# Grove_-_Differential_Amplifier_v1_2.net
KiCad netlist of a schematic drawn in EAGLE
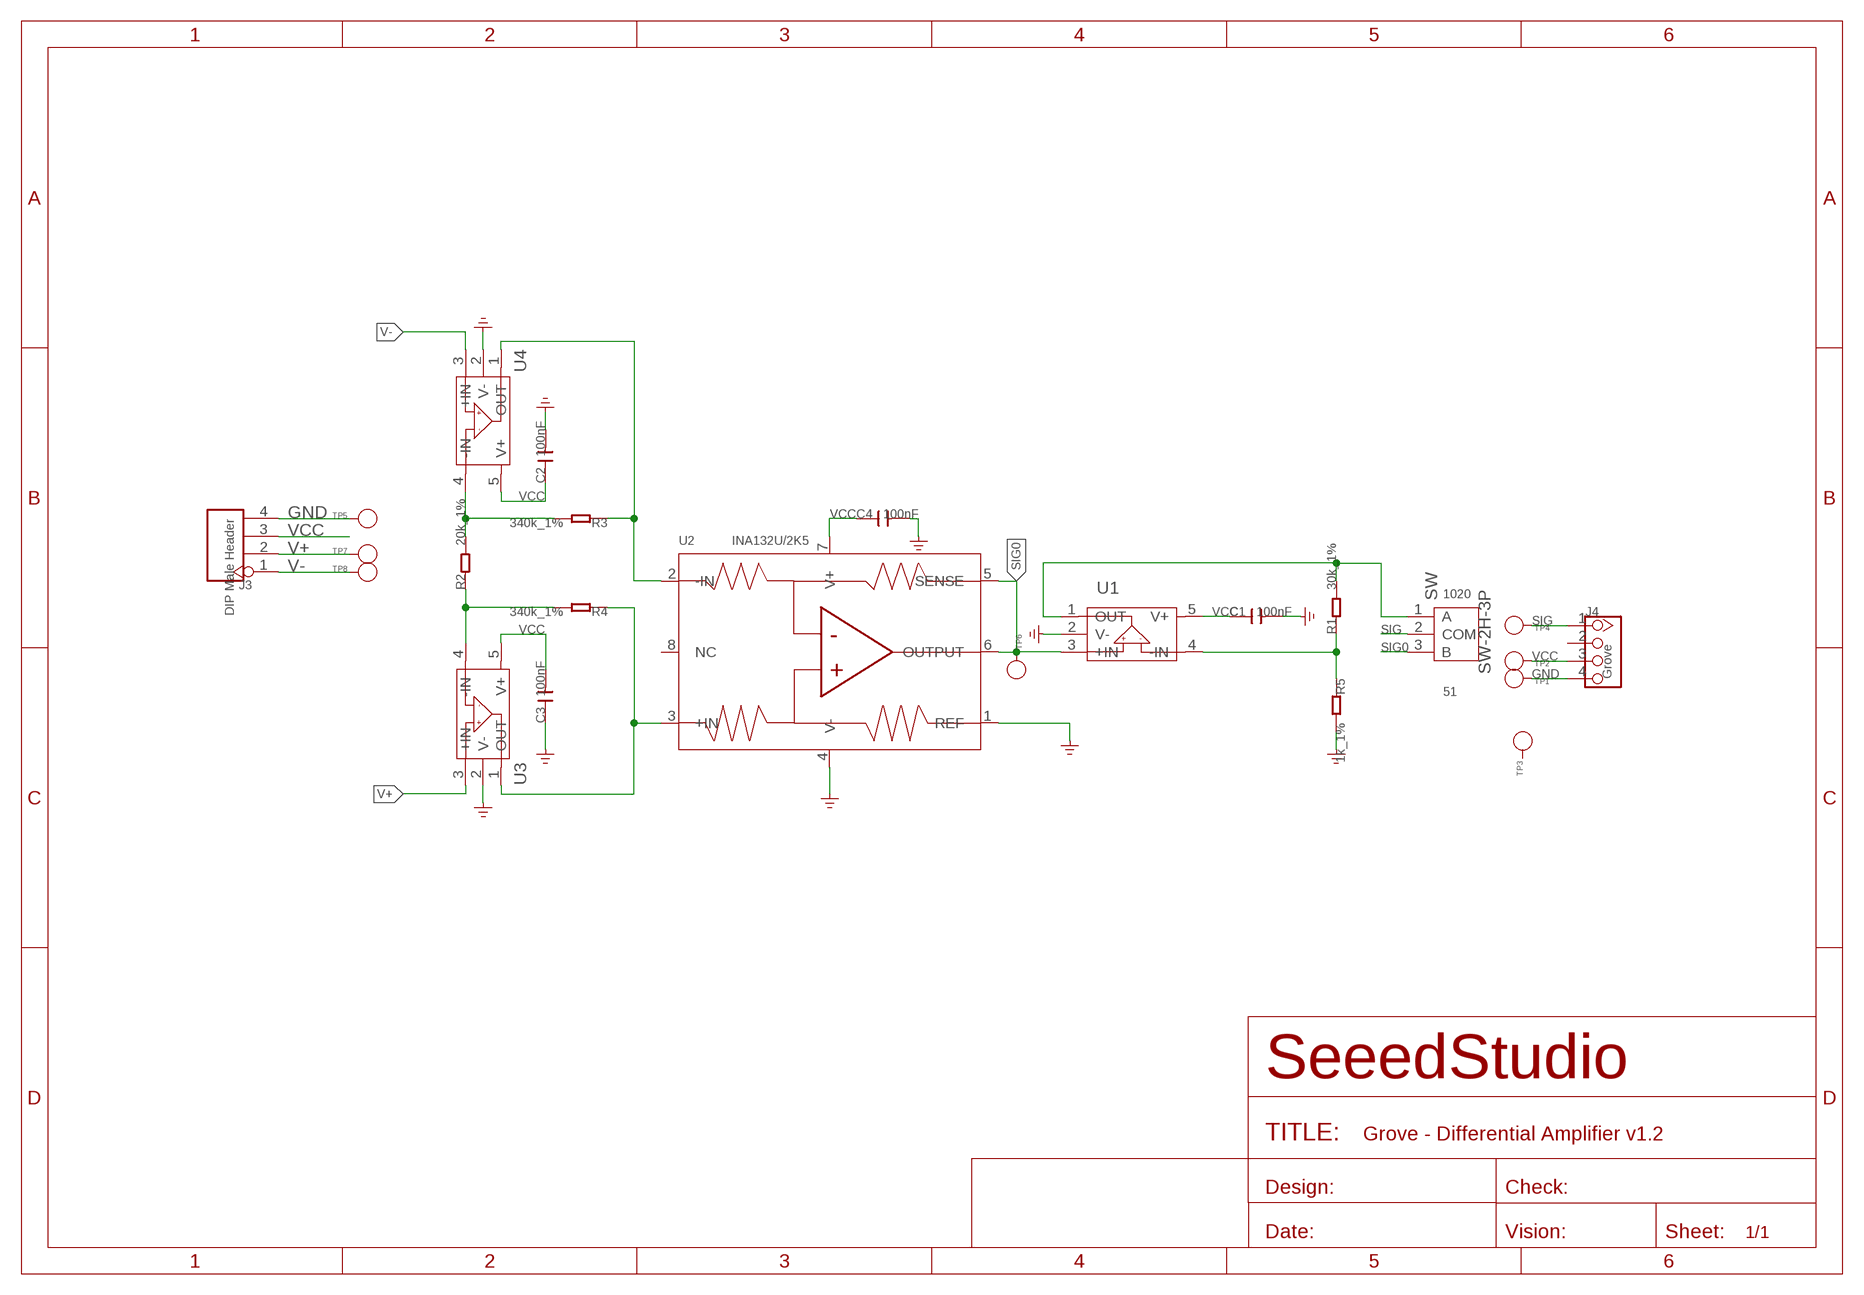
[diagram p0: schematic, sheet 1]

(export (version "E")
  (design (tool "Eeschema 10.0.6"))
  (components
    (comp (ref "C1")
      (value "100nF")
      (footprint "eagle-import:C0603")
      (libsource (lib "eagle-import") (part "C-0603"))
    )
    (comp (ref "C2")
      (value "100nF")
      (footprint "eagle-import:C0603")
      (libsource (lib "eagle-import") (part "C-0603"))
    )
    (comp (ref "C3")
      (value "100nF")
      (footprint "eagle-import:C0603")
      (libsource (lib "eagle-import") (part "C-0603"))
    )
    (comp (ref "C4")
      (value "100nF")
      (footprint "eagle-import:C0603")
      (libsource (lib "eagle-import") (part "C-0603"))
    )
    (comp (ref "J3")
      (value "DIP Male Header")
      (footprint "eagle-import:4P-65_35MIL")
      (libsource (lib "eagle-import") (part "HEADER-4P-65/35MIL"))
    )
    (comp (ref "J4")
      (value "Grove")
      (footprint "eagle-import:4P-2.0")
      (libsource (lib "eagle-import") (part "TWIG-4P-2.0-2.0"))
    )
    (comp (ref "R1")
      (value "30k_1%")
      (footprint "eagle-import:R0603")
      (libsource (lib "eagle-import") (part "R-0603"))
    )
    (comp (ref "R2")
      (value "20k_1%")
      (footprint "eagle-import:R0603")
      (libsource (lib "eagle-import") (part "R-0603"))
    )
    (comp (ref "R3")
      (value "340k_1%")
      (footprint "eagle-import:R0603")
      (libsource (lib "eagle-import") (part "R-0603"))
    )
    (comp (ref "R4")
      (value "340k_1%")
      (footprint "eagle-import:R0603")
      (libsource (lib "eagle-import") (part "R-0603"))
    )
    (comp (ref "R5")
      (value "1k_1%")
      (footprint "eagle-import:R0603")
      (libsource (lib "eagle-import") (part "R-0603"))
    )
    (comp (ref "SW")
      (value "SW-2H-3P")
      (footprint "eagle-import:3P-2CH-3.54X8.5")
      (libsource (lib "eagle-import") (part "SWITCH-2H-3P'--'"))
    )
    (comp (ref "TP1")
      (value "PAD-TEST-POINT'4545'")
      (footprint "eagle-import:TP_4545")
      (fields (field (name "PARTNO") "DNP"))
      (libsource (lib "eagle-import") (part "PAD-TEST-POINT'4545'"))
    )
    (comp (ref "TP2")
      (value "PAD-TEST-POINT'4545'")
      (footprint "eagle-import:TP_4545")
      (fields (field (name "PARTNO") "DNP"))
      (libsource (lib "eagle-import") (part "PAD-TEST-POINT'4545'"))
    )
    (comp (ref "TP3")
      (value "PAD-TEST-POINT'4545'")
      (footprint "eagle-import:TP_4545")
      (fields (field (name "PARTNO") "DNP"))
      (libsource (lib "eagle-import") (part "PAD-TEST-POINT'4545'"))
    )
    (comp (ref "TP4")
      (value "PAD-TEST-POINT'4545'")
      (footprint "eagle-import:TP_4545")
      (fields (field (name "PARTNO") "DNP"))
      (libsource (lib "eagle-import") (part "PAD-TEST-POINT'4545'"))
    )
    (comp (ref "TP5")
      (value "PAD-TEST-POINT'4545'")
      (footprint "eagle-import:TP_4545")
      (fields (field (name "PARTNO") "DNP"))
      (libsource (lib "eagle-import") (part "PAD-TEST-POINT'4545'"))
    )
    (comp (ref "TP6")
      (value "PAD-TEST-POINT'4545'")
      (footprint "eagle-import:TP_4545")
      (fields (field (name "PARTNO") "DNP"))
      (libsource (lib "eagle-import") (part "PAD-TEST-POINT'4545'"))
    )
    (comp (ref "TP7")
      (value "PAD-TEST-POINT'4545'")
      (footprint "eagle-import:TP_4545")
      (fields (field (name "PARTNO") "DNP"))
      (libsource (lib "eagle-import") (part "PAD-TEST-POINT'4545'"))
    )
    (comp (ref "TP8")
      (value "PAD-TEST-POINT'4545'")
      (footprint "eagle-import:TP_4545")
      (fields (field (name "PARTNO") "DNP"))
      (libsource (lib "eagle-import") (part "PAD-TEST-POINT'4545'"))
    )
    (comp (ref "U1")
      (value "OPA333DBV")
      (footprint "eagle-import:SOT23-5")
      (libsource (lib "eagle-import") (part "OPA333DBV"))
    )
    (comp (ref "U2")
      (value "INA132U/2K5")
      (footprint "eagle-import:SOIC8-6.0")
      (libsource (lib "eagle-import") (part "INA132U/2K5"))
    )
    (comp (ref "U3")
      (value "OPA333DBV")
      (footprint "eagle-import:SOT23-5")
      (libsource (lib "eagle-import") (part "OPA333DBV"))
    )
    (comp (ref "U4")
      (value "OPA333DBV")
      (footprint "eagle-import:SOT23-5")
      (libsource (lib "eagle-import") (part "OPA333DBV"))
    )
  )
  (nets
    (net (code "1") (name "/SIG") (class "Default")
      (node (ref "J4") (pin "1") (pinfunction "1_1") (pintype "bidirectional"))
      (node (ref "SW") (pin "2") (pinfunction "COM_2") (pintype "bidirectional"))
      (node (ref "TP4") (pin "T") (pinfunction "T_T") (pintype "bidirectional"))
    )
    (net (code "2") (name "/VCC") (class "Default")
      (node (ref "C1") (pin "1") (pinfunction "1_1") (pintype "passive"))
      (node (ref "C2") (pin "1") (pinfunction "1_1") (pintype "passive"))
      (node (ref "C3") (pin "2") (pinfunction "2_2") (pintype "passive"))
      (node (ref "C4") (pin "1") (pinfunction "1_1") (pintype "passive"))
      (node (ref "J3") (pin "3") (pinfunction "P$3_3") (pintype "bidirectional"))
      (node (ref "J4") (pin "3") (pinfunction "3_3") (pintype "bidirectional"))
      (node (ref "TP2") (pin "T") (pinfunction "T_T") (pintype "bidirectional"))
      (node (ref "U1") (pin "5") (pinfunction "V+_5") (pintype "bidirectional"))
      (node (ref "U2") (pin "7") (pinfunction "V+_7") (pintype "bidirectional"))
      (node (ref "U3") (pin "5") (pinfunction "V+_5") (pintype "bidirectional"))
      (node (ref "U4") (pin "5") (pinfunction "V+_5") (pintype "bidirectional"))
    )
    (net (code "3") (name "GND_POWER") (class "Default")
      (node (ref "C1") (pin "2") (pinfunction "2_2") (pintype "passive"))
      (node (ref "C2") (pin "2") (pinfunction "2_2") (pintype "passive"))
      (node (ref "C3") (pin "1") (pinfunction "1_1") (pintype "passive"))
      (node (ref "C4") (pin "2") (pinfunction "2_2") (pintype "passive"))
      (node (ref "J3") (pin "4") (pinfunction "P$4_4") (pintype "bidirectional"))
      (node (ref "J4") (pin "4") (pinfunction "4_4") (pintype "bidirectional"))
      (node (ref "R5") (pin "2") (pinfunction "2_2") (pintype "passive"))
      (node (ref "TP1") (pin "T") (pinfunction "T_T") (pintype "bidirectional"))
      (node (ref "TP5") (pin "T") (pinfunction "T_T") (pintype "bidirectional"))
      (node (ref "U1") (pin "2") (pinfunction "V-_2") (pintype "bidirectional"))
      (node (ref "U2") (pin "1") (pinfunction "REF_1") (pintype "bidirectional"))
      (node (ref "U2") (pin "4") (pinfunction "V-_4") (pintype "bidirectional"))
      (node (ref "U3") (pin "2") (pinfunction "V-_2") (pintype "bidirectional"))
      (node (ref "U4") (pin "2") (pinfunction "V-_2") (pintype "bidirectional"))
    )
    (net (code "4") (name "Net-(SW-A)") (class "Default")
      (node (ref "R1") (pin "2") (pinfunction "2_2") (pintype "passive"))
      (node (ref "SW") (pin "1") (pinfunction "A_1") (pintype "bidirectional"))
      (node (ref "U1") (pin "1") (pinfunction "OUT_1") (pintype "bidirectional"))
    )
    (net (code "5") (name "Net-(U1--IN)") (class "Default")
      (node (ref "R1") (pin "1") (pinfunction "1_1") (pintype "passive"))
      (node (ref "R5") (pin "1") (pinfunction "1_1") (pintype "passive"))
      (node (ref "U1") (pin "4") (pinfunction "-IN_4") (pintype "bidirectional"))
    )
    (net (code "6") (name "Net-(U2-+IN)") (class "Default")
      (node (ref "R4") (pin "1") (pinfunction "1_1") (pintype "passive"))
      (node (ref "U2") (pin "3") (pinfunction "+IN_3") (pintype "bidirectional"))
      (node (ref "U3") (pin "1") (pinfunction "OUT_1") (pintype "bidirectional"))
    )
    (net (code "7") (name "Net-(U2--IN)") (class "Default")
      (node (ref "R3") (pin "1") (pinfunction "1_1") (pintype "passive"))
      (node (ref "U2") (pin "2") (pinfunction "-IN_2") (pintype "bidirectional"))
      (node (ref "U4") (pin "1") (pinfunction "OUT_1") (pintype "bidirectional"))
    )
    (net (code "8") (name "Net-(U3--IN)") (class "Default")
      (node (ref "R2") (pin "1") (pinfunction "1_1") (pintype "passive"))
      (node (ref "R4") (pin "2") (pinfunction "2_2") (pintype "passive"))
      (node (ref "U3") (pin "4") (pinfunction "-IN_4") (pintype "bidirectional"))
    )
    (net (code "9") (name "Net-(U4--IN)") (class "Default")
      (node (ref "R2") (pin "2") (pinfunction "2_2") (pintype "passive"))
      (node (ref "R3") (pin "2") (pinfunction "2_2") (pintype "passive"))
      (node (ref "U4") (pin "4") (pinfunction "-IN_4") (pintype "bidirectional"))
    )
    (net (code "10") (name "SIG0") (class "Default")
      (node (ref "SW") (pin "3") (pinfunction "B_3") (pintype "bidirectional"))
      (node (ref "TP6") (pin "T") (pinfunction "T_T") (pintype "bidirectional"))
      (node (ref "U1") (pin "3") (pinfunction "+IN_3") (pintype "bidirectional"))
      (node (ref "U2") (pin "5") (pinfunction "SENSE_5") (pintype "bidirectional"))
      (node (ref "U2") (pin "6") (pinfunction "OUTPUT_6") (pintype "bidirectional"))
    )
    (net (code "11") (name "V+") (class "Default")
      (node (ref "J3") (pin "2") (pinfunction "P$2_2") (pintype "bidirectional"))
      (node (ref "TP7") (pin "T") (pinfunction "T_T") (pintype "bidirectional"))
      (node (ref "U3") (pin "3") (pinfunction "+IN_3") (pintype "bidirectional"))
    )
    (net (code "12") (name "V-") (class "Default")
      (node (ref "J3") (pin "1") (pinfunction "P$1_1") (pintype "bidirectional"))
      (node (ref "TP8") (pin "T") (pinfunction "T_T") (pintype "bidirectional"))
      (node (ref "U4") (pin "3") (pinfunction "+IN_3") (pintype "bidirectional"))
    )
    (net (code "13") (name "unconnected-(J4-Pad2)") (class "Default")
      (node (ref "J4") (pin "2") (pinfunction "2_2") (pintype "bidirectional"))
    )
    (net (code "14") (name "unconnected-(TP3-PadT)") (class "Default")
      (node (ref "TP3") (pin "T") (pinfunction "T_T") (pintype "bidirectional"))
    )
    (net (code "15") (name "unconnected-(U2-NC-Pad8)") (class "Default")
      (node (ref "U2") (pin "8") (pinfunction "NC_8") (pintype "bidirectional"))
    )
  )
)
